# Powder_O_Matic_Stepper_TMC2208_V1.net
KiCad netlist of a schematic drawn in EasyEDA
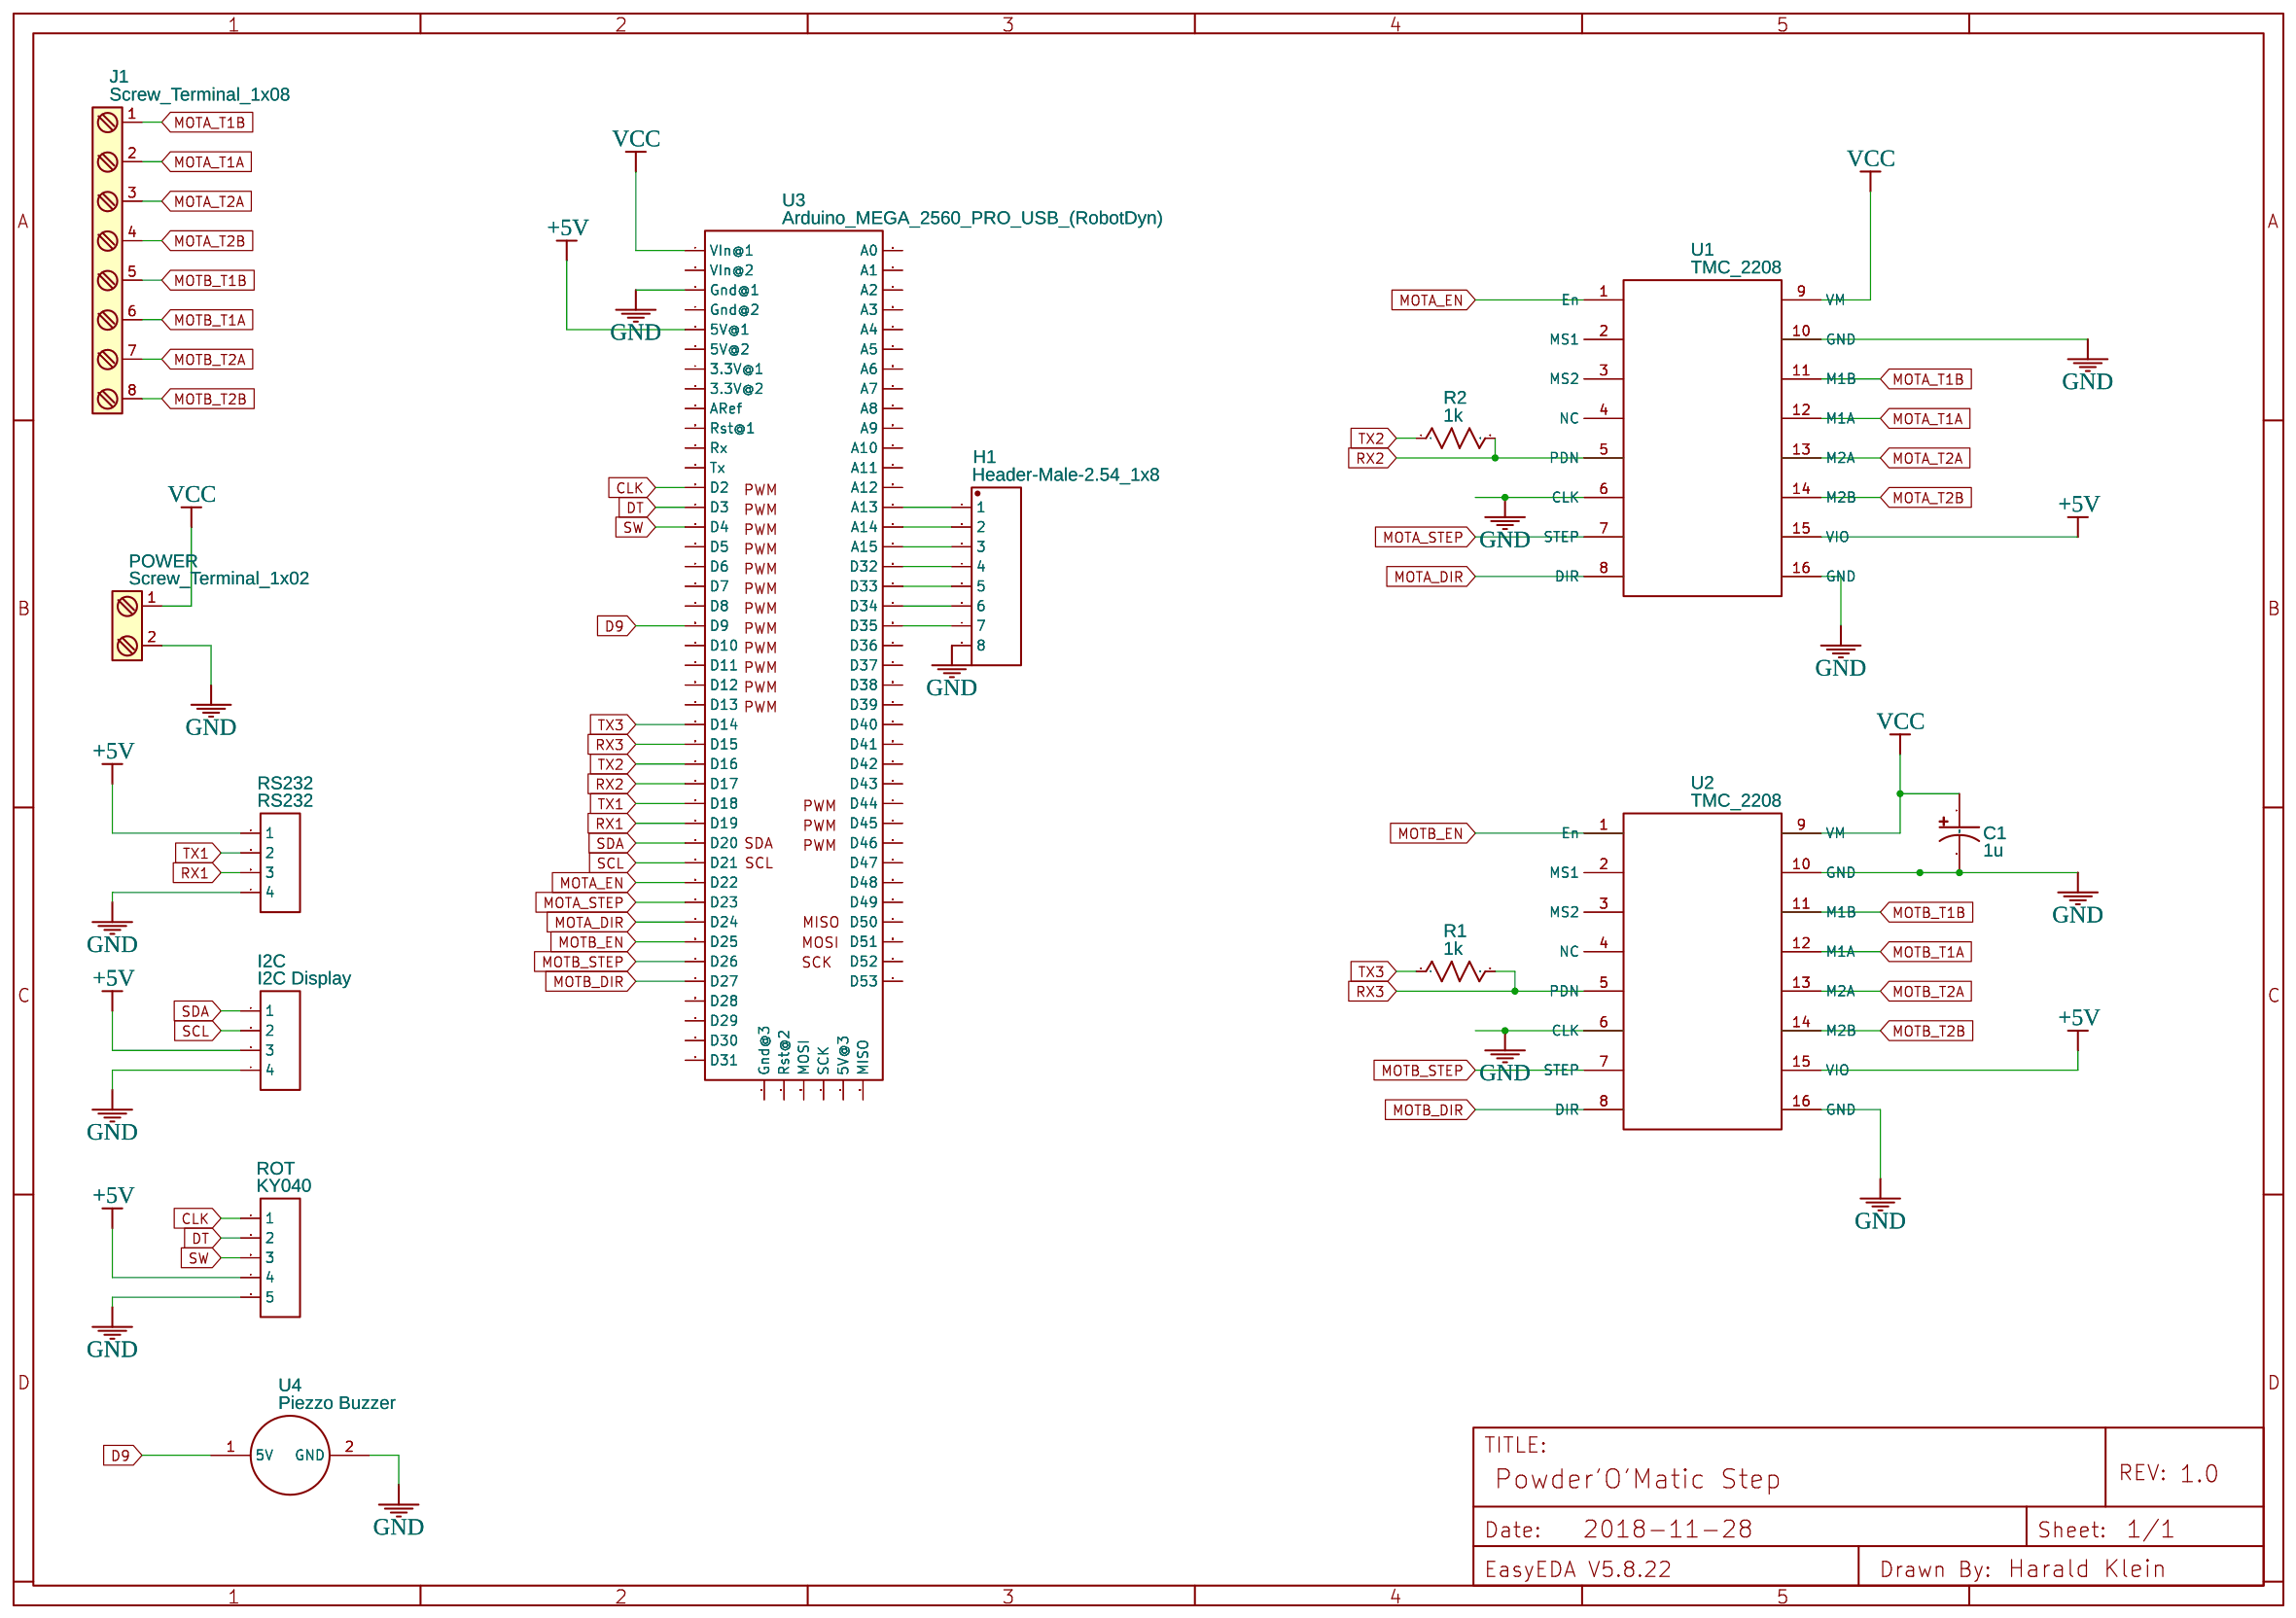
[diagram p0: schematic sheet]

(export (version "E")
  (design (tool "Eeschema 10.0.6"))
  (components
    (comp (ref "C1")
      (value "1u")
      (fields (field (name "BOM_Manufacturer Part") "?"))
      (libsource (lib "") (part "Cap_Electrolytic(TH)_D3.0XF1.5_US"))
    )
    (comp (ref "H1")
      (value "Header-Male-2.54_1x8")
      (fields
        (field (name "BOM_Manufacturer Part") "210S-1*8P L=11.6MMGold-plated black")
        (field (name "BOM_Supplier Part") "C124381")
      )
      (libsource (lib "") (part "Unknown_495_285"))
    )
    (comp (ref "I2C")
      (value "I2C Display")
      (fields
        (field (name "BOM_Manufacturer Part") "Header-Female-2.54_1x4")
        (field (name "BOM_Supplier Part") "C124413")
      )
      (libsource (lib "") (part "Unknown_130_520"))
    )
    (comp (ref "J1")
      (value "Screw_Terminal_1x08")
      (fields (field (name "BOM_Manufacturer Part") "?"))
      (libsource (lib "") (part "Unknown_55_55"))
    )
    (comp (ref "POWER")
      (value "Screw_Terminal_1x02")
      (fields (field (name "BOM_Manufacturer Part") "?"))
      (libsource (lib "") (part "Unknown_65_300"))
    )
    (comp (ref "R1")
      (value "1k")
      (fields (field (name "BOM_Manufacturer Part") "?"))
      (libsource (lib "") (part "Res_AXIAL-0.3(1/8W)_US"))
    )
    (comp (ref "R2")
      (value "1k")
      (fields (field (name "BOM_Manufacturer Part") "?"))
      (libsource (lib "") (part "Res_AXIAL-0.3(1/8W)_US"))
    )
    (comp (ref "ROT")
      (value "KY040")
      (fields
        (field (name "BOM_Manufacturer Part") "2.54mm 1*5p Female header")
        (field (name "BOM_Supplier Part") "C50950")
      )
      (libsource (lib "") (part "Unknown_125_630"))
    )
    (comp (ref "RS232")
      (value "RS232")
      (fields
        (field (name "BOM_Manufacturer Part") "Header-Female-2.54_1x4")
        (field (name "BOM_Supplier Part") "C124413")
      )
      (libsource (lib "") (part "Unknown_130_430"))
    )
    (comp (ref "U1")
      (value "TMC_2208")
      (fields (field (name "BOM_Manufacturer Part") "?"))
      (libsource (lib "") (part "Unknown_855_205"))
    )
    (comp (ref "U2")
      (value "TMC_2208")
      (fields (field (name "BOM_Manufacturer Part") "?"))
      (libsource (lib "") (part "Unknown_855_475"))
    )
    (comp (ref "U3")
      (value "Arduino_MEGA_2560_PRO_USB_(RobotDyn)")
      (fields (field (name "BOM_Manufacturer Part") "ARDUINO MEGA 2560 PRO EMBED (RobotDyn)"))
      (libsource (lib "") (part "Unknown_390_330"))
    )
    (comp (ref "U4")
      (value "Piezzo Buzzer")
      (fields (field (name "BOM_Manufacturer Part") "New SchematicLib"))
      (libsource (lib "") (part "Unknown_145_720"))
    )
  )
  (nets
    (net (code "1") (name "+5V") (class "Default")
      (node (ref "I2C") (pin "3") (pinfunction "3_3") (pintype "input"))
      (node (ref "ROT") (pin "4") (pinfunction "4_4") (pintype "input"))
      (node (ref "RS232") (pin "1") (pinfunction "1_1") (pintype "input"))
      (node (ref "U1") (pin "15") (pinfunction "VIO_15") (pintype "unspecified"))
      (node (ref "U2") (pin "15") (pinfunction "VIO_15") (pintype "unspecified"))
      (node (ref "U3") (pin "5") (pinfunction "5V@1_5") (pintype "unspecified"))
    )
    (net (code "2") (name "CLK") (class "Default")
      (node (ref "ROT") (pin "1") (pinfunction "1_1") (pintype "input"))
      (node (ref "U3") (pin "13") (pinfunction "D2_13") (pintype "unspecified"))
    )
    (net (code "3") (name "D9") (class "Default")
      (node (ref "U3") (pin "20") (pinfunction "D9_20") (pintype "unspecified"))
      (node (ref "U4") (pin "1") (pinfunction "5V_1") (pintype "unspecified"))
    )
    (net (code "4") (name "DT") (class "Default")
      (node (ref "ROT") (pin "2") (pinfunction "2_2") (pintype "input"))
      (node (ref "U3") (pin "14") (pinfunction "D3_14") (pintype "unspecified"))
    )
    (net (code "5") (name "GND") (class "Default")
      (node (ref "C1") (pin "2") (pinfunction "2_2") (pintype "unspecified"))
      (node (ref "H1") (pin "8") (pinfunction "8_8") (pintype "unspecified"))
      (node (ref "I2C") (pin "4") (pinfunction "4_4") (pintype "input"))
      (node (ref "POWER") (pin "2") (pintype "unspecified"))
      (node (ref "ROT") (pin "5") (pinfunction "5_5") (pintype "input"))
      (node (ref "RS232") (pin "4") (pinfunction "4_4") (pintype "input"))
      (node (ref "U1") (pin "10") (pinfunction "GND_10") (pintype "unspecified"))
      (node (ref "U1") (pin "16") (pinfunction "GND_16") (pintype "unspecified"))
      (node (ref "U1") (pin "6") (pinfunction "CLK_6") (pintype "unspecified"))
      (node (ref "U2") (pin "10") (pinfunction "GND_10") (pintype "unspecified"))
      (node (ref "U2") (pin "16") (pinfunction "GND_16") (pintype "unspecified"))
      (node (ref "U2") (pin "6") (pinfunction "CLK_6") (pintype "unspecified"))
      (node (ref "U3") (pin "3") (pinfunction "Gnd@1_3") (pintype "unspecified"))
      (node (ref "U4") (pin "2") (pinfunction "GND_2") (pintype "unspecified"))
    )
    (net (code "6") (name "MOTA_DIR") (class "Default")
      (node (ref "U1") (pin "8") (pinfunction "DIR_8") (pintype "unspecified"))
      (node (ref "U3") (pin "35") (pinfunction "D24_35") (pintype "unspecified"))
    )
    (net (code "7") (name "MOTA_EN") (class "Default")
      (node (ref "U1") (pin "1") (pinfunction "En_1") (pintype "unspecified"))
      (node (ref "U3") (pin "33") (pinfunction "D22_33") (pintype "unspecified"))
    )
    (net (code "8") (name "MOTA_STEP") (class "Default")
      (node (ref "U1") (pin "7") (pinfunction "STEP_7") (pintype "unspecified"))
      (node (ref "U3") (pin "34") (pinfunction "D23_34") (pintype "unspecified"))
    )
    (net (code "9") (name "MOTA_T1A") (class "Default")
      (node (ref "J1") (pin "2") (pintype "unspecified"))
      (node (ref "U1") (pin "12") (pinfunction "M1A_12") (pintype "unspecified"))
    )
    (net (code "10") (name "MOTA_T1B") (class "Default")
      (node (ref "J1") (pin "1") (pintype "unspecified"))
      (node (ref "U1") (pin "11") (pinfunction "M1B_11") (pintype "unspecified"))
    )
    (net (code "11") (name "MOTA_T2A") (class "Default")
      (node (ref "J1") (pin "3") (pintype "unspecified"))
      (node (ref "U1") (pin "13") (pinfunction "M2A_13") (pintype "unspecified"))
    )
    (net (code "12") (name "MOTA_T2B") (class "Default")
      (node (ref "J1") (pin "4") (pintype "unspecified"))
      (node (ref "U1") (pin "14") (pinfunction "M2B_14") (pintype "unspecified"))
    )
    (net (code "13") (name "MOTB_DIR") (class "Default")
      (node (ref "U2") (pin "8") (pinfunction "DIR_8") (pintype "unspecified"))
      (node (ref "U3") (pin "38") (pinfunction "D27_38") (pintype "unspecified"))
    )
    (net (code "14") (name "MOTB_EN") (class "Default")
      (node (ref "U2") (pin "1") (pinfunction "En_1") (pintype "unspecified"))
      (node (ref "U3") (pin "36") (pinfunction "D25_36") (pintype "unspecified"))
    )
    (net (code "15") (name "MOTB_STEP") (class "Default")
      (node (ref "U2") (pin "7") (pinfunction "STEP_7") (pintype "unspecified"))
      (node (ref "U3") (pin "37") (pinfunction "D26_37") (pintype "unspecified"))
    )
    (net (code "16") (name "MOTB_T1A") (class "Default")
      (node (ref "J1") (pin "6") (pintype "unspecified"))
      (node (ref "U2") (pin "12") (pinfunction "M1A_12") (pintype "unspecified"))
    )
    (net (code "17") (name "MOTB_T1B") (class "Default")
      (node (ref "J1") (pin "5") (pintype "unspecified"))
      (node (ref "U2") (pin "11") (pinfunction "M1B_11") (pintype "unspecified"))
    )
    (net (code "18") (name "MOTB_T2A") (class "Default")
      (node (ref "J1") (pin "7") (pintype "unspecified"))
      (node (ref "U2") (pin "13") (pinfunction "M2A_13") (pintype "unspecified"))
    )
    (net (code "19") (name "MOTB_T2B") (class "Default")
      (node (ref "J1") (pin "8") (pintype "unspecified"))
      (node (ref "U2") (pin "14") (pinfunction "M2B_14") (pintype "unspecified"))
    )
    (net (code "20") (name "Net-(U3-A13)") (class "Default")
      (node (ref "H1") (pin "1") (pinfunction "1_1") (pintype "unspecified"))
      (node (ref "U3") (pin "56") (pinfunction "A13_56") (pintype "unspecified"))
    )
    (net (code "21") (name "Net-(U3-A14)") (class "Default")
      (node (ref "H1") (pin "2") (pinfunction "2_2") (pintype "unspecified"))
      (node (ref "U3") (pin "57") (pinfunction "A14_57") (pintype "unspecified"))
    )
    (net (code "22") (name "Net-(U3-A15)") (class "Default")
      (node (ref "H1") (pin "3") (pinfunction "3_3") (pintype "unspecified"))
      (node (ref "U3") (pin "58") (pinfunction "A15_58") (pintype "unspecified"))
    )
    (net (code "23") (name "Net-(U3-D32)") (class "Default")
      (node (ref "H1") (pin "4") (pinfunction "4_4") (pintype "unspecified"))
      (node (ref "U3") (pin "59") (pinfunction "D32_59") (pintype "unspecified"))
    )
    (net (code "24") (name "Net-(U3-D33)") (class "Default")
      (node (ref "H1") (pin "5") (pinfunction "5_5") (pintype "unspecified"))
      (node (ref "U3") (pin "60") (pinfunction "D33_60") (pintype "unspecified"))
    )
    (net (code "25") (name "Net-(U3-D34)") (class "Default")
      (node (ref "H1") (pin "6") (pinfunction "6_6") (pintype "unspecified"))
      (node (ref "U3") (pin "61") (pinfunction "D34_61") (pintype "unspecified"))
    )
    (net (code "26") (name "Net-(U3-D35)") (class "Default")
      (node (ref "H1") (pin "7") (pinfunction "7_7") (pintype "unspecified"))
      (node (ref "U3") (pin "62") (pinfunction "D35_62") (pintype "unspecified"))
    )
    (net (code "27") (name "RX1") (class "Default")
      (node (ref "RS232") (pin "3") (pinfunction "3_3") (pintype "input"))
      (node (ref "U3") (pin "30") (pinfunction "D19_30") (pintype "unspecified"))
    )
    (net (code "28") (name "RX2") (class "Default")
      (node (ref "R2") (pin "2") (pinfunction "2_2") (pintype "unspecified"))
      (node (ref "U1") (pin "5") (pinfunction "PDN_5") (pintype "unspecified"))
      (node (ref "U3") (pin "28") (pinfunction "D17_28") (pintype "unspecified"))
    )
    (net (code "29") (name "RX3") (class "Default")
      (node (ref "R1") (pin "2") (pinfunction "2_2") (pintype "unspecified"))
      (node (ref "U2") (pin "5") (pinfunction "PDN_5") (pintype "unspecified"))
      (node (ref "U3") (pin "26") (pinfunction "D15_26") (pintype "unspecified"))
    )
    (net (code "30") (name "SCL") (class "Default")
      (node (ref "I2C") (pin "2") (pinfunction "2_2") (pintype "input"))
      (node (ref "U3") (pin "32") (pinfunction "D21_32") (pintype "unspecified"))
    )
    (net (code "31") (name "SDA") (class "Default")
      (node (ref "I2C") (pin "1") (pinfunction "1_1") (pintype "input"))
      (node (ref "U3") (pin "31") (pinfunction "D20_31") (pintype "unspecified"))
    )
    (net (code "32") (name "SW") (class "Default")
      (node (ref "ROT") (pin "3") (pinfunction "3_3") (pintype "input"))
      (node (ref "U3") (pin "15") (pinfunction "D4_15") (pintype "unspecified"))
    )
    (net (code "33") (name "TX1") (class "Default")
      (node (ref "RS232") (pin "2") (pinfunction "2_2") (pintype "input"))
      (node (ref "U3") (pin "29") (pinfunction "D18_29") (pintype "unspecified"))
    )
    (net (code "34") (name "TX2") (class "Default")
      (node (ref "R2") (pin "1") (pinfunction "1_1") (pintype "unspecified"))
      (node (ref "U3") (pin "27") (pinfunction "D16_27") (pintype "unspecified"))
    )
    (net (code "35") (name "TX3") (class "Default")
      (node (ref "R1") (pin "1") (pinfunction "1_1") (pintype "unspecified"))
      (node (ref "U3") (pin "25") (pinfunction "D14_25") (pintype "unspecified"))
    )
    (net (code "36") (name "VCC") (class "Default")
      (node (ref "C1") (pin "1") (pinfunction "1_1") (pintype "unspecified"))
      (node (ref "POWER") (pin "1") (pintype "unspecified"))
      (node (ref "U1") (pin "9") (pinfunction "VM_9") (pintype "unspecified"))
      (node (ref "U2") (pin "9") (pinfunction "VM_9") (pintype "unspecified"))
      (node (ref "U3") (pin "1") (pinfunction "VIn@1_1") (pintype "unspecified"))
    )
    (net (code "37") (name "unconnected-(U1-MS1-Pad2)") (class "Default")
      (node (ref "U1") (pin "2") (pinfunction "MS1_2") (pintype "unspecified"))
    )
    (net (code "38") (name "unconnected-(U1-MS2-Pad3)") (class "Default")
      (node (ref "U1") (pin "3") (pinfunction "MS2_3") (pintype "unspecified"))
    )
    (net (code "39") (name "unconnected-(U1-NC-Pad4)") (class "Default")
      (node (ref "U1") (pin "4") (pinfunction "NC_4") (pintype "unspecified"))
    )
    (net (code "40") (name "unconnected-(U2-MS1-Pad2)") (class "Default")
      (node (ref "U2") (pin "2") (pinfunction "MS1_2") (pintype "unspecified"))
    )
    (net (code "41") (name "unconnected-(U2-MS2-Pad3)") (class "Default")
      (node (ref "U2") (pin "3") (pinfunction "MS2_3") (pintype "unspecified"))
    )
    (net (code "42") (name "unconnected-(U2-NC-Pad4)") (class "Default")
      (node (ref "U2") (pin "4") (pinfunction "NC_4") (pintype "unspecified"))
    )
    (net (code "43") (name "unconnected-(U3-3.3V@1-Pad7)") (class "Default")
      (node (ref "U3") (pin "7") (pinfunction "3.3V@1_7") (pintype "unspecified"))
    )
    (net (code "44") (name "unconnected-(U3-3.3V@2-Pad8)") (class "Default")
      (node (ref "U3") (pin "8") (pinfunction "3.3V@2_8") (pintype "unspecified"))
    )
    (net (code "45") (name "unconnected-(U3-5V@2-Pad6)") (class "Default")
      (node (ref "U3") (pin "6") (pinfunction "5V@2_6") (pintype "unspecified"))
    )
    (net (code "46") (name "unconnected-(U3-5V@3-Pad81)") (class "Default")
      (node (ref "U3") (pin "81") (pinfunction "5V@3_81") (pintype "unspecified"))
    )
    (net (code "47") (name "unconnected-(U3-A0-Pad43)") (class "Default")
      (node (ref "U3") (pin "43") (pinfunction "A0_43") (pintype "unspecified"))
    )
    (net (code "48") (name "unconnected-(U3-A1-Pad44)") (class "Default")
      (node (ref "U3") (pin "44") (pinfunction "A1_44") (pintype "unspecified"))
    )
    (net (code "49") (name "unconnected-(U3-A2-Pad45)") (class "Default")
      (node (ref "U3") (pin "45") (pinfunction "A2_45") (pintype "unspecified"))
    )
    (net (code "50") (name "unconnected-(U3-A3-Pad46)") (class "Default")
      (node (ref "U3") (pin "46") (pinfunction "A3_46") (pintype "unspecified"))
    )
    (net (code "51") (name "unconnected-(U3-A4-Pad47)") (class "Default")
      (node (ref "U3") (pin "47") (pinfunction "A4_47") (pintype "unspecified"))
    )
    (net (code "52") (name "unconnected-(U3-A5-Pad48)") (class "Default")
      (node (ref "U3") (pin "48") (pinfunction "A5_48") (pintype "unspecified"))
    )
    (net (code "53") (name "unconnected-(U3-A6-Pad49)") (class "Default")
      (node (ref "U3") (pin "49") (pinfunction "A6_49") (pintype "unspecified"))
    )
    (net (code "54") (name "unconnected-(U3-A7-Pad50)") (class "Default")
      (node (ref "U3") (pin "50") (pinfunction "A7_50") (pintype "unspecified"))
    )
    (net (code "55") (name "unconnected-(U3-A8-Pad51)") (class "Default")
      (node (ref "U3") (pin "51") (pinfunction "A8_51") (pintype "unspecified"))
    )
    (net (code "56") (name "unconnected-(U3-A9-Pad52)") (class "Default")
      (node (ref "U3") (pin "52") (pinfunction "A9_52") (pintype "unspecified"))
    )
    (net (code "57") (name "unconnected-(U3-A10-Pad53)") (class "Default")
      (node (ref "U3") (pin "53") (pinfunction "A10_53") (pintype "unspecified"))
    )
    (net (code "58") (name "unconnected-(U3-A11-Pad54)") (class "Default")
      (node (ref "U3") (pin "54") (pinfunction "A11_54") (pintype "unspecified"))
    )
    (net (code "59") (name "unconnected-(U3-A12-Pad55)") (class "Default")
      (node (ref "U3") (pin "55") (pinfunction "A12_55") (pintype "unspecified"))
    )
    (net (code "60") (name "unconnected-(U3-ARef-Pad9)") (class "Default")
      (node (ref "U3") (pin "9") (pinfunction "ARef_9") (pintype "unspecified"))
    )
    (net (code "61") (name "unconnected-(U3-D5-Pad16)") (class "Default")
      (node (ref "U3") (pin "16") (pinfunction "D5_16") (pintype "unspecified"))
    )
    (net (code "62") (name "unconnected-(U3-D6-Pad17)") (class "Default")
      (node (ref "U3") (pin "17") (pinfunction "D6_17") (pintype "unspecified"))
    )
    (net (code "63") (name "unconnected-(U3-D7-Pad18)") (class "Default")
      (node (ref "U3") (pin "18") (pinfunction "D7_18") (pintype "unspecified"))
    )
    (net (code "64") (name "unconnected-(U3-D8-Pad19)") (class "Default")
      (node (ref "U3") (pin "19") (pinfunction "D8_19") (pintype "unspecified"))
    )
    (net (code "65") (name "unconnected-(U3-D10-Pad21)") (class "Default")
      (node (ref "U3") (pin "21") (pinfunction "D10_21") (pintype "unspecified"))
    )
    (net (code "66") (name "unconnected-(U3-D11-Pad22)") (class "Default")
      (node (ref "U3") (pin "22") (pinfunction "D11_22") (pintype "unspecified"))
    )
    (net (code "67") (name "unconnected-(U3-D12-Pad23)") (class "Default")
      (node (ref "U3") (pin "23") (pinfunction "D12_23") (pintype "unspecified"))
    )
    (net (code "68") (name "unconnected-(U3-D13-Pad24)") (class "Default")
      (node (ref "U3") (pin "24") (pinfunction "D13_24") (pintype "unspecified"))
    )
    (net (code "69") (name "unconnected-(U3-D28-Pad39)") (class "Default")
      (node (ref "U3") (pin "39") (pinfunction "D28_39") (pintype "unspecified"))
    )
    (net (code "70") (name "unconnected-(U3-D29-Pad40)") (class "Default")
      (node (ref "U3") (pin "40") (pinfunction "D29_40") (pintype "unspecified"))
    )
    (net (code "71") (name "unconnected-(U3-D30-Pad41)") (class "Default")
      (node (ref "U3") (pin "41") (pinfunction "D30_41") (pintype "unspecified"))
    )
    (net (code "72") (name "unconnected-(U3-D31-Pad42)") (class "Default")
      (node (ref "U3") (pin "42") (pinfunction "D31_42") (pintype "unspecified"))
    )
    (net (code "73") (name "unconnected-(U3-D36-Pad63)") (class "Default")
      (node (ref "U3") (pin "63") (pinfunction "D36_63") (pintype "unspecified"))
    )
    (net (code "74") (name "unconnected-(U3-D37-Pad64)") (class "Default")
      (node (ref "U3") (pin "64") (pinfunction "D37_64") (pintype "unspecified"))
    )
    (net (code "75") (name "unconnected-(U3-D38-Pad65)") (class "Default")
      (node (ref "U3") (pin "65") (pinfunction "D38_65") (pintype "unspecified"))
    )
    (net (code "76") (name "unconnected-(U3-D39-Pad66)") (class "Default")
      (node (ref "U3") (pin "66") (pinfunction "D39_66") (pintype "unspecified"))
    )
    (net (code "77") (name "unconnected-(U3-D40-Pad67)") (class "Default")
      (node (ref "U3") (pin "67") (pinfunction "D40_67") (pintype "unspecified"))
    )
    (net (code "78") (name "unconnected-(U3-D41-Pad68)") (class "Default")
      (node (ref "U3") (pin "68") (pinfunction "D41_68") (pintype "unspecified"))
    )
    (net (code "79") (name "unconnected-(U3-D42-Pad69)") (class "Default")
      (node (ref "U3") (pin "69") (pinfunction "D42_69") (pintype "unspecified"))
    )
    (net (code "80") (name "unconnected-(U3-D43-Pad70)") (class "Default")
      (node (ref "U3") (pin "70") (pinfunction "D43_70") (pintype "unspecified"))
    )
    (net (code "81") (name "unconnected-(U3-D44-Pad71)") (class "Default")
      (node (ref "U3") (pin "71") (pinfunction "D44_71") (pintype "unspecified"))
    )
    (net (code "82") (name "unconnected-(U3-D45-Pad72)") (class "Default")
      (node (ref "U3") (pin "72") (pinfunction "D45_72") (pintype "unspecified"))
    )
    (net (code "83") (name "unconnected-(U3-D46-Pad73)") (class "Default")
      (node (ref "U3") (pin "73") (pinfunction "D46_73") (pintype "unspecified"))
    )
    (net (code "84") (name "unconnected-(U3-D47-Pad74)") (class "Default")
      (node (ref "U3") (pin "74") (pinfunction "D47_74") (pintype "unspecified"))
    )
    (net (code "85") (name "unconnected-(U3-D48-Pad75)") (class "Default")
      (node (ref "U3") (pin "75") (pinfunction "D48_75") (pintype "unspecified"))
    )
    (net (code "86") (name "unconnected-(U3-D49-Pad76)") (class "Default")
      (node (ref "U3") (pin "76") (pinfunction "D49_76") (pintype "unspecified"))
    )
    (net (code "87") (name "unconnected-(U3-D50-Pad77)") (class "Default")
      (node (ref "U3") (pin "77") (pinfunction "D50_77") (pintype "unspecified"))
    )
    (net (code "88") (name "unconnected-(U3-D51-Pad78)") (class "Default")
      (node (ref "U3") (pin "78") (pinfunction "D51_78") (pintype "unspecified"))
    )
    (net (code "89") (name "unconnected-(U3-D52-Pad79)") (class "Default")
      (node (ref "U3") (pin "79") (pinfunction "D52_79") (pintype "unspecified"))
    )
    (net (code "90") (name "unconnected-(U3-D53-Pad80)") (class "Default")
      (node (ref "U3") (pin "80") (pinfunction "D53_80") (pintype "unspecified"))
    )
    (net (code "91") (name "unconnected-(U3-Gnd@2-Pad4)") (class "Default")
      (node (ref "U3") (pin "4") (pinfunction "Gnd@2_4") (pintype "unspecified"))
    )
    (net (code "92") (name "unconnected-(U3-Gnd@3-Pad85)") (class "Default")
      (node (ref "U3") (pin "85") (pinfunction "Gnd@3_85") (pintype "unspecified"))
    )
    (net (code "93") (name "unconnected-(U3-MISO-Pad82)") (class "Default")
      (node (ref "U3") (pin "82") (pinfunction "MISO_82") (pintype "unspecified"))
    )
    (net (code "94") (name "unconnected-(U3-MOSI-Pad83)") (class "Default")
      (node (ref "U3") (pin "83") (pinfunction "MOSI_83") (pintype "unspecified"))
    )
    (net (code "95") (name "unconnected-(U3-Rst@1-Pad10)") (class "Default")
      (node (ref "U3") (pin "10") (pinfunction "Rst@1_10") (pintype "unspecified"))
    )
    (net (code "96") (name "unconnected-(U3-Rst@2-Pad86)") (class "Default")
      (node (ref "U3") (pin "86") (pinfunction "Rst@2_86") (pintype "unspecified"))
    )
    (net (code "97") (name "unconnected-(U3-Rx-Pad11)") (class "Default")
      (node (ref "U3") (pin "11") (pinfunction "Rx_11") (pintype "unspecified"))
    )
    (net (code "98") (name "unconnected-(U3-SCK-Pad84)") (class "Default")
      (node (ref "U3") (pin "84") (pinfunction "SCK_84") (pintype "unspecified"))
    )
    (net (code "99") (name "unconnected-(U3-Tx-Pad12)") (class "Default")
      (node (ref "U3") (pin "12") (pinfunction "Tx_12") (pintype "unspecified"))
    )
    (net (code "100") (name "unconnected-(U3-VIn@2-Pad2)") (class "Default")
      (node (ref "U3") (pin "2") (pinfunction "VIn@2_2") (pintype "unspecified"))
    )
  )
)
